# ESP-PCM1822Q1-breakout.net
KiCad netlist of a schematic drawn in Altium Designer
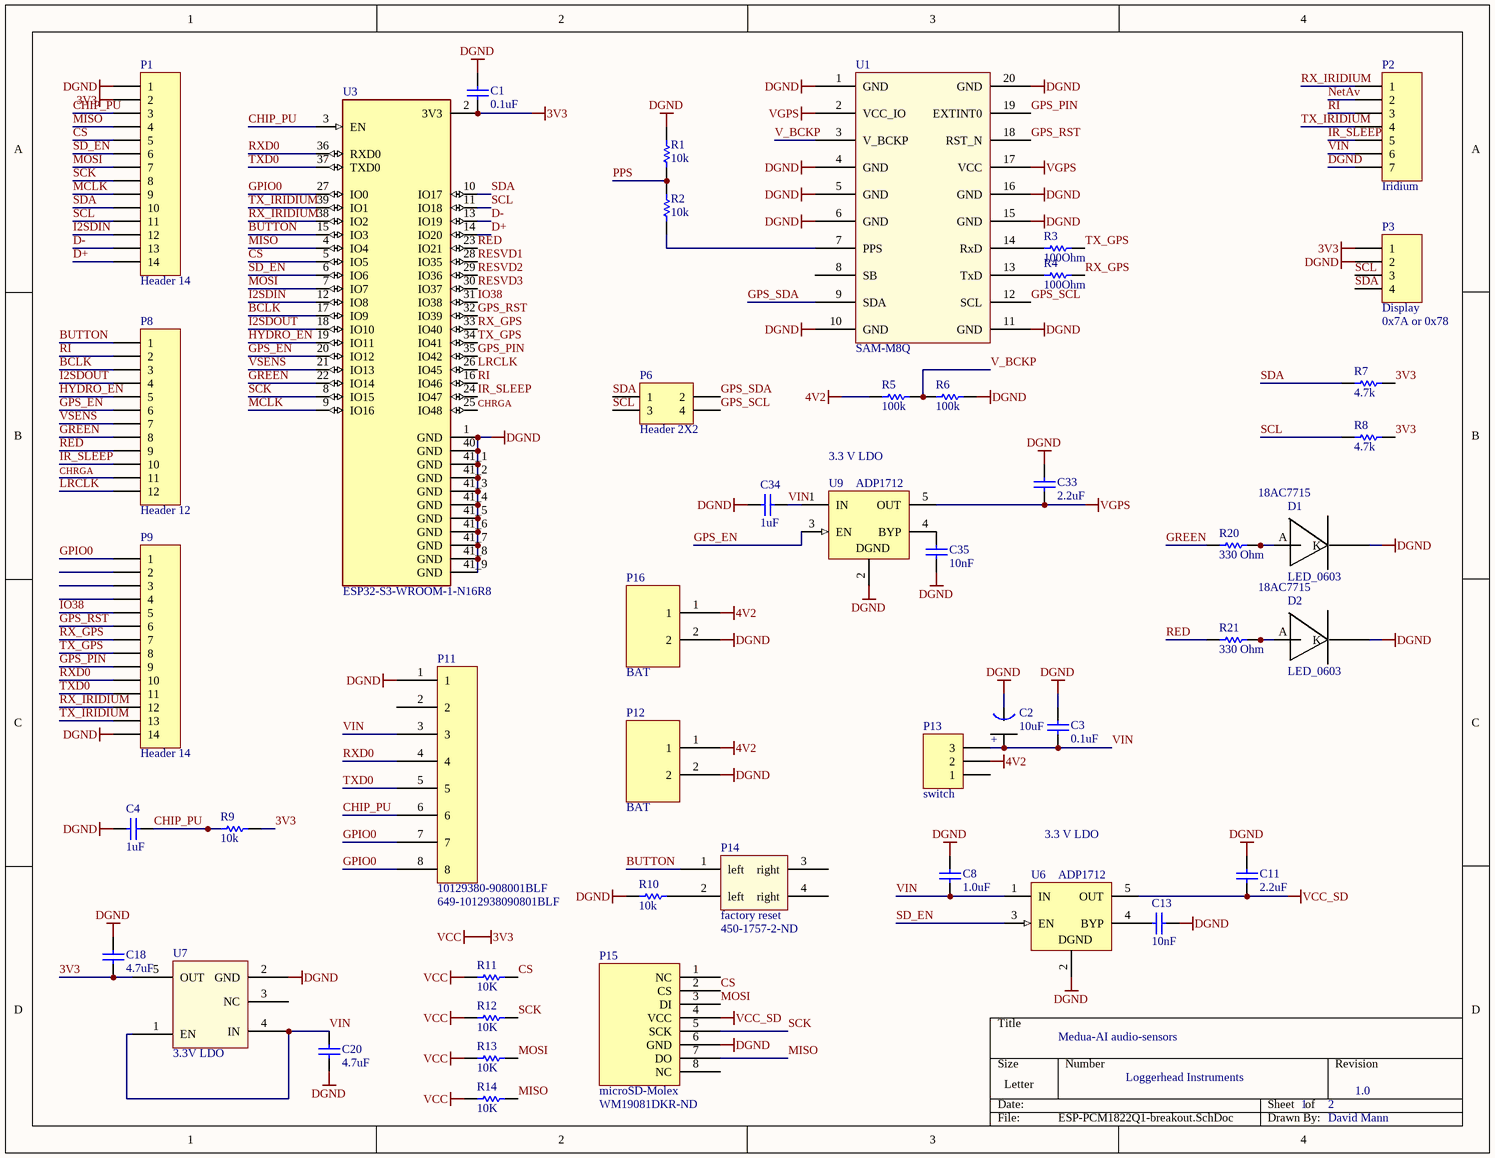
[diagram p0: ESP-PCM1822Q1-breakout.SchDoc]

(export (version "E")
  (design (tool "Eeschema 10.0.6"))
  (components
    (comp (ref "C1")
      (value "0.1uF")
      (footprint "0402")
      (description "Ceramic Chip Capacitor - Standard")
      (fields (field (name "PUBLISHER") "Altium Limited"))
      (libsource (lib "KEMET Chip Capacitor") (part "C0402"))
    )
    (comp (ref "C2") (value "10uF") (footprint "Tant0805") (libsource (lib "Loggerhead") (part "Tant0805")))
    (comp (ref "C3")
      (value "0.1uF")
      (footprint "0402")
      (description "Ceramic Chip Capacitor - Standard")
      (fields (field (name "PUBLISHER") "Altium Limited"))
      (libsource (lib "KEMET Chip Capacitor") (part "C0402"))
    )
    (comp (ref "C4")
      (value "1uF")
      (footprint "0402")
      (description "Ceramic Chip Capacitor - Standard")
      (fields (field (name "PUBLISHER") "Altium Limited"))
      (libsource (lib "KEMET Chip Capacitor") (part "C0402"))
    )
    (comp (ref "C8")
      (value "1.0uF")
      (footprint "0402")
      (description "Ceramic Chip Capacitor - Standard")
      (fields (field (name "PUBLISHER") "Altium Limited"))
      (libsource (lib "KEMET Chip Capacitor") (part "C0402"))
    )
    (comp (ref "C11")
      (value "2.2uF")
      (footprint "0402")
      (description "Ceramic Chip Capacitor - Standard")
      (fields (field (name "PUBLISHER") "Altium Limited"))
      (libsource (lib "KEMET Chip Capacitor") (part "C0402"))
    )
    (comp (ref "C13")
      (value "10nF")
      (footprint "0402")
      (description "Ceramic Chip Capacitor - Standard")
      (fields (field (name "PUBLISHER") "Altium Limited"))
      (libsource (lib "KEMET Chip Capacitor") (part "C0402"))
    )
    (comp (ref "C18")
      (value "4.7uF")
      (footprint "0402")
      (description "Ceramic Chip Capacitor - Standard")
      (fields (field (name "PUBLISHER") "Altium Limited"))
      (libsource (lib "KEMET Chip Capacitor") (part "C0402"))
    )
    (comp (ref "C20")
      (value "4.7uF")
      (footprint "0402")
      (description "Ceramic Chip Capacitor - Standard")
      (fields (field (name "PUBLISHER") "Altium Limited"))
      (libsource (lib "KEMET Chip Capacitor") (part "C0402"))
    )
    (comp (ref "C33")
      (value "2.2uF")
      (footprint "0402")
      (description "Ceramic Chip Capacitor - Standard")
      (fields (field (name "PUBLISHER") "Altium Limited"))
      (libsource (lib "KEMET Chip Capacitor") (part "C0402"))
    )
    (comp (ref "C34")
      (value "1uF")
      (footprint "0402")
      (description "Ceramic Chip Capacitor - Standard")
      (fields (field (name "PUBLISHER") "Altium Limited"))
      (libsource (lib "KEMET Chip Capacitor") (part "C0402"))
    )
    (comp (ref "C35")
      (value "10nF")
      (footprint "0402")
      (description "Ceramic Chip Capacitor - Standard")
      (fields (field (name "PUBLISHER") "Altium Limited"))
      (libsource (lib "KEMET Chip Capacitor") (part "C0402"))
    )
    (comp (ref "D1")
      (value "LED_0603")
      (footprint "Diode0603")
      (fields (field (name "SUPPLIER PART NUMBER 1") "18AC7715"))
      (libsource (lib "Loggerhead") (part "LED_0603"))
    )
    (comp (ref "D2")
      (value "LED_0603")
      (footprint "Diode0603")
      (fields (field (name "SUPPLIER PART NUMBER 1") "18AC7715"))
      (libsource (lib "Loggerhead") (part "LED_0603"))
    )
    (comp (ref "P1")
      (value "Header 14")
      (footprint "HDR1X14")
      (description "Header, 14-Pin")
      (fields (field (name "PUBLISHER") "Altium Limited"))
      (libsource (lib "Miscellaneous Connectors") (part "Header 14"))
    )
    (comp (ref "P2")
      (value "Iridium")
      (footprint "HDR1X7")
      (description "Header, 7-Pin")
      (fields (field (name "PUBLISHER") "Altium Limited"))
      (libsource (lib "Miscellaneous Connectors") (part "Header 7"))
    )
    (comp (ref "P3")
      (value "Display")
      (footprint "HDR1X4")
      (description "Header, 4-Pin")
      (fields (field (name "PUBLISHER") "Altium Limited"))
      (libsource (lib "Miscellaneous Connectors") (part "Header 4"))
    )
    (comp (ref "P6")
      (value "Header 2X2")
      (footprint "HDR2X2")
      (description "Header, 2-Pin, Dual row")
      (fields (field (name "PUBLISHER") "Altium Limited"))
      (libsource (lib "Miscellaneous Connectors") (part "Header 2X2"))
    )
    (comp (ref "P8")
      (value "Header 12")
      (footprint "HDR1X12")
      (description "Header, 12-Pin")
      (fields (field (name "PUBLISHER") "Altium Limited"))
      (libsource (lib "Miscellaneous Connectors") (part "Header 12"))
    )
    (comp (ref "P9")
      (value "Header 14")
      (footprint "HDR1X14")
      (description "Header, 14-Pin")
      (fields (field (name "PUBLISHER") "Altium Limited"))
      (libsource (lib "Miscellaneous Connectors") (part "Header 14"))
    )
    (comp (ref "P11")
      (value "10129380-908001BLF")
      (footprint "Header_8_SMT")
      (description "Surface mount header")
      (fields (field (name "SUPPLIER PART NUMBER 1") "649-1012938090801BLF"))
      (libsource (lib "Loggerhead") (part "Header8_SMT"))
    )
    (comp (ref "P12")
      (value "BAT")
      (footprint "HDR_2x1_2mm")
      (libsource (lib "Loggerhead") (part "HDR_2x1_2mm"))
    )
    (comp (ref "P13")
      (value "switch")
      (footprint "HDR1X3")
      (description "Header, 3-Pin")
      (fields (field (name "PUBLISHER") "Altium Limited"))
      (libsource (lib "Miscellaneous Connectors") (part "Header 3"))
    )
    (comp (ref "P14")
      (value "factory reset")
      (footprint "SOP4")
      (fields (field (name "SUPPLIER PART NUMBER 1") "450-1757-2-ND"))
      (libsource (lib "Loggerhead") (part "pushbutton"))
    )
    (comp (ref "P15")
      (value "microSD-Molex")
      (footprint "microSD_Molex_hinged")
      (fields (field (name "SUPPLIER PART NUMBER 1") "WM19081DKR-ND"))
      (libsource (lib "Loggerhead") (part "microSD_Molex_hinged"))
    )
    (comp (ref "P16")
      (value "BAT")
      (footprint "HDR_2x1_2mm")
      (libsource (lib "Loggerhead") (part "HDR_2x1_2mm"))
    )
    (comp (ref "R1")
      (value "10k")
      (footprint "3-0603")
      (fields (field (name "PUBLISHER") "Altium Limited"))
      (libsource (lib "Panasonic Resistor") (part "ERJ3RK"))
    )
    (comp (ref "R2")
      (value "10k")
      (footprint "3-0603")
      (fields (field (name "PUBLISHER") "Altium Limited"))
      (libsource (lib "Panasonic Resistor") (part "ERJ3RK"))
    )
    (comp (ref "R3")
      (value "100Ohm")
      (footprint "2-0402")
      (fields (field (name "PUBLISHER") "Altium Limited"))
      (libsource (lib "Panasonic Resistor") (part "ERJ2RB"))
    )
    (comp (ref "R4")
      (value "100Ohm")
      (footprint "2-0402")
      (fields (field (name "PUBLISHER") "Altium Limited"))
      (libsource (lib "Panasonic Resistor") (part "ERJ2RB"))
    )
    (comp (ref "R5")
      (value "100k")
      (footprint "3-0603")
      (fields (field (name "PUBLISHER") "Altium Limited"))
      (libsource (lib "Panasonic Resistor") (part "ERJ3RK"))
    )
    (comp (ref "R6")
      (value "100k")
      (footprint "3-0603")
      (fields (field (name "PUBLISHER") "Altium Limited"))
      (libsource (lib "Panasonic Resistor") (part "ERJ3RK"))
    )
    (comp (ref "R7")
      (value "4.7k")
      (footprint "3-0603")
      (fields (field (name "PUBLISHER") "Altium Limited"))
      (libsource (lib "Panasonic Resistor") (part "ERJ3RK"))
    )
    (comp (ref "R8")
      (value "4.7k")
      (footprint "3-0603")
      (fields (field (name "PUBLISHER") "Altium Limited"))
      (libsource (lib "Panasonic Resistor") (part "ERJ3RK"))
    )
    (comp (ref "R9")
      (value "10k")
      (footprint "2-0402")
      (fields (field (name "PUBLISHER") "Altium Limited"))
      (libsource (lib "Panasonic Resistor") (part "ERJ2RB"))
    )
    (comp (ref "R10")
      (value "10k")
      (footprint "2-0402")
      (fields (field (name "PUBLISHER") "Altium Limited"))
      (libsource (lib "Panasonic Resistor") (part "ERJ2RB"))
    )
    (comp (ref "R11")
      (value "10K")
      (footprint "3-0603")
      (fields (field (name "PUBLISHER") "Altium Limited"))
      (libsource (lib "Panasonic Resistor") (part "ERJ3EK"))
    )
    (comp (ref "R12")
      (value "10K")
      (footprint "3-0603")
      (fields (field (name "PUBLISHER") "Altium Limited"))
      (libsource (lib "Panasonic Resistor") (part "ERJ3EK"))
    )
    (comp (ref "R13")
      (value "10K")
      (footprint "3-0603")
      (fields (field (name "PUBLISHER") "Altium Limited"))
      (libsource (lib "Panasonic Resistor") (part "ERJ3EK"))
    )
    (comp (ref "R14")
      (value "10K")
      (footprint "3-0603")
      (fields (field (name "PUBLISHER") "Altium Limited"))
      (libsource (lib "Panasonic Resistor") (part "ERJ3EK"))
    )
    (comp (ref "R20")
      (value "330 Ohm")
      (footprint "2-0402")
      (fields (field (name "PUBLISHER") "Altium Limited"))
      (libsource (lib "Panasonic Resistor") (part "ERJ2RB"))
    )
    (comp (ref "R21")
      (value "330 Ohm")
      (footprint "2-0402")
      (fields (field (name "PUBLISHER") "Altium Limited"))
      (libsource (lib "Panasonic Resistor") (part "ERJ2RB"))
    )
    (comp (ref "U1")
      (value "SAM-M8Q")
      (footprint "GPS SAM-MQ8")
      (libsource (lib "Loggerhead") (part "GPS SAM-M8Q"))
    )
    (comp (ref "U3")
      (value "ESP32-S3-WROOM-1-N16R8")
      (footprint "XCVR_ESP32-S3-WROOM-1-N16R2")
      (description "Bluetooth, WiFi 802.11b/g/n, Bluetooth v5.0 Transceiver Module 2.4GHz PCB Trace Surface Mount")
      (fields (field (name "MP") "ESP32-S3-WROOM-1-N16R2") (field (name "MF") "Espressif Systems"))
      (libsource (lib "ESP32-S3-WROOM-1-N16R2") (part "ESP32-S3-WROOM-1-N16R2"))
    )
    (comp (ref "U6")
      (value "ADP1712")
      (footprint "MF05A_N")
      (description "Micropower, 150mA Low-Noise Ultra Low-Dropout CMOS Voltage Regulator")
      (fields
        (field (name "PARTNUMBER") "LP3985IM5-3.3")
        (field (name "MANUFACTURER") "National Semiconductor")
        (field (name "PUBLISHER") "Altium Limited")
      )
      (libsource (lib "NSC LDO") (part "LP3985IM5-3.3"))
    )
    (comp (ref "U7")
      (value "3.3V LDO")
      (footprint "AP7361C-33Y5-13")
      (libsource (lib "Loggerhead") (part "AP7361C-33Y5-13"))
    )
    (comp (ref "U9")
      (value "ADP1712")
      (footprint "MF05A_N")
      (description "Micropower, 150mA Low-Noise Ultra Low-Dropout CMOS Voltage Regulator")
      (fields
        (field (name "PARTNUMBER") "LP3985IM5-3.3")
        (field (name "MANUFACTURER") "National Semiconductor")
        (field (name "PUBLISHER") "Altium Limited")
      )
      (libsource (lib "NSC LDO") (part "LP3985IM5-3.3"))
    )
  )
  (nets
    (net (code "1") (name "/BCLK") (class "Default")
      (node (ref "P8") (pin "3") (pinfunction "3_3") (pintype "passive"))
      (node (ref "U3") (pin "17") (pinfunction "IO9_17") (pintype "bidirectional"))
    )
    (net (code "2") (name "/BUTTON") (class "Default")
      (node (ref "P14") (pin "1") (pinfunction "left_1") (pintype "passive"))
      (node (ref "P8") (pin "1") (pinfunction "1_1") (pintype "passive"))
      (node (ref "U3") (pin "15") (pinfunction "IO3_15") (pintype "bidirectional"))
    )
    (net (code "3") (name "/CHIP_PU") (class "Default")
      (node (ref "C4") (pin "1") (pinfunction "1_1") (pintype "passive"))
      (node (ref "P1") (pin "3") (pinfunction "3_3") (pintype "passive"))
      (node (ref "P11") (pin "6") (pinfunction "6_6") (pintype "passive"))
      (node (ref "R9") (pin "2") (pinfunction "2_2") (pintype "passive"))
      (node (ref "U3") (pin "3") (pinfunction "EN_3") (pintype "input"))
    )
    (net (code "4") (name "/CHRGA") (class "Default")
      (node (ref "P8") (pin "11") (pinfunction "11_11") (pintype "passive"))
      (node (ref "U3") (pin "25") (pinfunction "IO48_25") (pintype "bidirectional"))
    )
    (net (code "5") (name "/CS") (class "Default")
      (node (ref "P1") (pin "5") (pinfunction "5_5") (pintype "passive"))
      (node (ref "P15") (pin "2") (pinfunction "CS_2") (pintype "passive"))
      (node (ref "R11") (pin "2") (pinfunction "2_2") (pintype "passive"))
      (node (ref "U3") (pin "5") (pinfunction "IO5_5") (pintype "bidirectional"))
    )
    (net (code "6") (name "/D+") (class "Default")
      (node (ref "P1") (pin "14") (pinfunction "14_14") (pintype "passive"))
      (node (ref "U3") (pin "14") (pinfunction "IO20_14") (pintype "bidirectional"))
    )
    (net (code "7") (name "/D-") (class "Default")
      (node (ref "P1") (pin "13") (pinfunction "13_13") (pintype "passive"))
      (node (ref "U3") (pin "13") (pinfunction "IO19_13") (pintype "bidirectional"))
    )
    (net (code "8") (name "/GPIO0") (class "Default")
      (node (ref "P11") (pin "7") (pinfunction "7_7") (pintype "passive"))
      (node (ref "P11") (pin "8") (pinfunction "8_8") (pintype "passive"))
      (node (ref "P9") (pin "1") (pinfunction "1_1") (pintype "passive"))
      (node (ref "U3") (pin "27") (pinfunction "IO0_27") (pintype "bidirectional"))
    )
    (net (code "9") (name "/GPS_EN") (class "Default")
      (node (ref "P8") (pin "6") (pinfunction "6_6") (pintype "passive"))
      (node (ref "U3") (pin "20") (pinfunction "IO12_20") (pintype "bidirectional"))
      (node (ref "U9") (pin "3") (pinfunction "EN_3") (pintype "input"))
    )
    (net (code "10") (name "/GPS_PIN") (class "Default")
      (node (ref "P9") (pin "9") (pinfunction "9_9") (pintype "passive"))
      (node (ref "U1") (pin "19") (pinfunction "EXTINT0_19") (pintype "passive"))
      (node (ref "U3") (pin "35") (pinfunction "IO42_35") (pintype "bidirectional"))
    )
    (net (code "11") (name "/GPS_RST") (class "Default")
      (node (ref "P9") (pin "6") (pinfunction "6_6") (pintype "passive"))
      (node (ref "U1") (pin "18") (pinfunction "RST_N_18") (pintype "passive"))
      (node (ref "U3") (pin "32") (pinfunction "IO39_32") (pintype "bidirectional"))
    )
    (net (code "12") (name "/GPS_SCL") (class "Default")
      (node (ref "P6") (pin "4") (pinfunction "4_4") (pintype "passive"))
      (node (ref "U1") (pin "12") (pinfunction "SCL_12") (pintype "passive"))
    )
    (net (code "13") (name "/GPS_SDA") (class "Default")
      (node (ref "P6") (pin "2") (pinfunction "2_2") (pintype "passive"))
      (node (ref "U1") (pin "9") (pinfunction "SDA_9") (pintype "passive"))
    )
    (net (code "14") (name "/GREEN") (class "Default")
      (node (ref "P8") (pin "8") (pinfunction "8_8") (pintype "passive"))
      (node (ref "R20") (pin "2") (pinfunction "2_2") (pintype "passive"))
      (node (ref "U3") (pin "22") (pinfunction "IO14_22") (pintype "bidirectional"))
    )
    (net (code "15") (name "/HYDRO_EN") (class "Default")
      (node (ref "P8") (pin "5") (pinfunction "5_5") (pintype "passive"))
      (node (ref "U3") (pin "19") (pinfunction "IO11_19") (pintype "bidirectional"))
    )
    (net (code "16") (name "/I2SDIN") (class "Default")
      (node (ref "P1") (pin "12") (pinfunction "12_12") (pintype "passive"))
      (node (ref "U3") (pin "12") (pinfunction "IO8_12") (pintype "bidirectional"))
    )
    (net (code "17") (name "/I2SDOUT") (class "Default")
      (node (ref "P8") (pin "4") (pinfunction "4_4") (pintype "passive"))
      (node (ref "U3") (pin "18") (pinfunction "IO10_18") (pintype "bidirectional"))
    )
    (net (code "18") (name "/IO38") (class "Default")
      (node (ref "P9") (pin "5") (pinfunction "5_5") (pintype "passive"))
      (node (ref "U3") (pin "31") (pinfunction "IO38_31") (pintype "bidirectional"))
    )
    (net (code "19") (name "/IR_SLEEP") (class "Default")
      (node (ref "P2") (pin "5") (pinfunction "5_5") (pintype "passive"))
      (node (ref "P8") (pin "10") (pinfunction "10_10") (pintype "passive"))
      (node (ref "U3") (pin "24") (pinfunction "IO47_24") (pintype "bidirectional"))
    )
    (net (code "20") (name "/LRCLK") (class "Default")
      (node (ref "P8") (pin "12") (pinfunction "12_12") (pintype "passive"))
      (node (ref "U3") (pin "26") (pinfunction "IO45_26") (pintype "bidirectional"))
    )
    (net (code "21") (name "/MCLK") (class "Default")
      (node (ref "P1") (pin "9") (pinfunction "9_9") (pintype "passive"))
      (node (ref "U3") (pin "9") (pinfunction "IO16_9") (pintype "bidirectional"))
    )
    (net (code "22") (name "/MISO") (class "Default")
      (node (ref "P1") (pin "4") (pinfunction "4_4") (pintype "passive"))
      (node (ref "P15") (pin "7") (pinfunction "DO_7") (pintype "passive"))
      (node (ref "R14") (pin "2") (pinfunction "2_2") (pintype "passive"))
      (node (ref "U3") (pin "4") (pinfunction "IO4_4") (pintype "bidirectional"))
    )
    (net (code "23") (name "/MOSI") (class "Default")
      (node (ref "P1") (pin "7") (pinfunction "7_7") (pintype "passive"))
      (node (ref "P15") (pin "3") (pinfunction "DI_3") (pintype "passive"))
      (node (ref "R13") (pin "2") (pinfunction "2_2") (pintype "passive"))
      (node (ref "U3") (pin "7") (pinfunction "IO7_7") (pintype "bidirectional"))
    )
    (net (code "24") (name "/NetAv") (class "Default")
      (node (ref "P2") (pin "2") (pinfunction "2_2") (pintype "passive"))
    )
    (net (code "25") (name "/PPS") (class "Default")
      (node (ref "R1") (pin "2") (pinfunction "2_2") (pintype "passive"))
      (node (ref "R2") (pin "1") (pinfunction "1_1") (pintype "passive"))
    )
    (net (code "26") (name "/RED") (class "Default")
      (node (ref "P8") (pin "9") (pinfunction "9_9") (pintype "passive"))
      (node (ref "R21") (pin "2") (pinfunction "2_2") (pintype "passive"))
      (node (ref "U3") (pin "23") (pinfunction "IO21_23") (pintype "bidirectional"))
    )
    (net (code "27") (name "/RESVD1") (class "Default")
      (node (ref "U3") (pin "28") (pinfunction "IO35_28") (pintype "bidirectional"))
    )
    (net (code "28") (name "/RESVD2") (class "Default")
      (node (ref "U3") (pin "29") (pinfunction "IO36_29") (pintype "bidirectional"))
    )
    (net (code "29") (name "/RESVD3") (class "Default")
      (node (ref "U3") (pin "30") (pinfunction "IO37_30") (pintype "bidirectional"))
    )
    (net (code "30") (name "/RI") (class "Default")
      (node (ref "P2") (pin "3") (pinfunction "3_3") (pintype "passive"))
      (node (ref "P8") (pin "2") (pinfunction "2_2") (pintype "passive"))
      (node (ref "U3") (pin "16") (pinfunction "IO46_16") (pintype "bidirectional"))
    )
    (net (code "31") (name "/RXD0") (class "Default")
      (node (ref "P11") (pin "4") (pinfunction "4_4") (pintype "passive"))
      (node (ref "P9") (pin "10") (pinfunction "10_10") (pintype "passive"))
      (node (ref "U3") (pin "36") (pinfunction "RXD0_36") (pintype "bidirectional"))
    )
    (net (code "32") (name "/RX_GPS") (class "Default")
      (node (ref "P9") (pin "7") (pinfunction "7_7") (pintype "passive"))
      (node (ref "R4") (pin "1") (pinfunction "1_1") (pintype "passive"))
      (node (ref "U3") (pin "33") (pinfunction "IO40_33") (pintype "bidirectional"))
    )
    (net (code "33") (name "/RX_IRIDIUM") (class "Default")
      (node (ref "P2") (pin "1") (pinfunction "1_1") (pintype "passive"))
      (node (ref "P9") (pin "12") (pinfunction "12_12") (pintype "passive"))
      (node (ref "U3") (pin "38") (pinfunction "IO2_38") (pintype "bidirectional"))
    )
    (net (code "34") (name "/SCK") (class "Default")
      (node (ref "P1") (pin "8") (pinfunction "8_8") (pintype "passive"))
      (node (ref "P15") (pin "5") (pinfunction "SCK_5") (pintype "passive"))
      (node (ref "R12") (pin "2") (pinfunction "2_2") (pintype "passive"))
      (node (ref "U3") (pin "8") (pinfunction "IO15_8") (pintype "bidirectional"))
    )
    (net (code "35") (name "/SCL") (class "Default")
      (node (ref "P1") (pin "11") (pinfunction "11_11") (pintype "passive"))
      (node (ref "P3") (pin "3") (pinfunction "3_3") (pintype "passive"))
      (node (ref "P6") (pin "3") (pinfunction "3_3") (pintype "passive"))
      (node (ref "R8") (pin "1") (pinfunction "1_1") (pintype "passive"))
      (node (ref "U3") (pin "11") (pinfunction "IO18_11") (pintype "bidirectional"))
    )
    (net (code "36") (name "/SDA") (class "Default")
      (node (ref "P1") (pin "10") (pinfunction "10_10") (pintype "passive"))
      (node (ref "P3") (pin "4") (pinfunction "4_4") (pintype "passive"))
      (node (ref "P6") (pin "1") (pinfunction "1_1") (pintype "passive"))
      (node (ref "R7") (pin "1") (pinfunction "1_1") (pintype "passive"))
      (node (ref "U3") (pin "10") (pinfunction "IO17_10") (pintype "bidirectional"))
    )
    (net (code "37") (name "/SD_EN") (class "Default")
      (node (ref "P1") (pin "6") (pinfunction "6_6") (pintype "passive"))
      (node (ref "U3") (pin "6") (pinfunction "IO6_6") (pintype "bidirectional"))
      (node (ref "U6") (pin "3") (pinfunction "EN_3") (pintype "input"))
    )
    (net (code "38") (name "/TXD0") (class "Default")
      (node (ref "P11") (pin "5") (pinfunction "5_5") (pintype "passive"))
      (node (ref "P9") (pin "11") (pinfunction "11_11") (pintype "passive"))
      (node (ref "U3") (pin "37") (pinfunction "TXD0_37") (pintype "bidirectional"))
    )
    (net (code "39") (name "/TX_GPS") (class "Default")
      (node (ref "P9") (pin "8") (pinfunction "8_8") (pintype "passive"))
      (node (ref "R3") (pin "1") (pinfunction "1_1") (pintype "passive"))
      (node (ref "U3") (pin "34") (pinfunction "IO41_34") (pintype "bidirectional"))
    )
    (net (code "40") (name "/TX_IRIDIUM") (class "Default")
      (node (ref "P2") (pin "4") (pinfunction "4_4") (pintype "passive"))
      (node (ref "P9") (pin "13") (pinfunction "13_13") (pintype "passive"))
      (node (ref "U3") (pin "39") (pinfunction "IO1_39") (pintype "bidirectional"))
    )
    (net (code "41") (name "/VIN") (class "Default")
      (node (ref "C2") (pin "2") (pinfunction "+_2") (pintype "passive"))
      (node (ref "C20") (pin "1") (pinfunction "1_1") (pintype "passive"))
      (node (ref "C3") (pin "1") (pinfunction "1_1") (pintype "passive"))
      (node (ref "C34") (pin "1") (pinfunction "1_1") (pintype "passive"))
      (node (ref "C8") (pin "1") (pinfunction "1_1") (pintype "passive"))
      (node (ref "P11") (pin "3") (pinfunction "3_3") (pintype "passive"))
      (node (ref "P13") (pin "3") (pinfunction "3_3") (pintype "passive"))
      (node (ref "P2") (pin "6") (pinfunction "6_6") (pintype "passive"))
      (node (ref "U6") (pin "1") (pinfunction "IN_1") (pintype "power_in"))
      (node (ref "U7") (pin "1") (pinfunction "EN_1") (pintype "passive"))
      (node (ref "U7") (pin "4") (pinfunction "IN_4") (pintype "passive"))
      (node (ref "U9") (pin "1") (pinfunction "IN_1") (pintype "power_in"))
    )
    (net (code "42") (name "/VSENS") (class "Default")
      (node (ref "P8") (pin "7") (pinfunction "7_7") (pintype "passive"))
      (node (ref "U3") (pin "21") (pinfunction "IO13_21") (pintype "bidirectional"))
    )
    (net (code "43") (name "/V_BCKP") (class "Default")
      (node (ref "R5") (pin "1") (pinfunction "1_1") (pintype "passive"))
      (node (ref "R6") (pin "2") (pinfunction "2_2") (pintype "passive"))
      (node (ref "U1") (pin "3") (pinfunction "V_BCKP_3") (pintype "passive"))
    )
    (net (code "44") (name "3V3") (class "Default")
      (node (ref "C1") (pin "1") (pinfunction "1_1") (pintype "passive"))
      (node (ref "C18") (pin "2") (pinfunction "2_2") (pintype "passive"))
      (node (ref "P1") (pin "2") (pinfunction "2_2") (pintype "passive"))
      (node (ref "P3") (pin "1") (pinfunction "1_1") (pintype "passive"))
      (node (ref "R11") (pin "1") (pinfunction "1_1") (pintype "passive"))
      (node (ref "R12") (pin "1") (pinfunction "1_1") (pintype "passive"))
      (node (ref "R13") (pin "1") (pinfunction "1_1") (pintype "passive"))
      (node (ref "R14") (pin "1") (pinfunction "1_1") (pintype "passive"))
      (node (ref "R7") (pin "2") (pinfunction "2_2") (pintype "passive"))
      (node (ref "R8") (pin "2") (pinfunction "2_2") (pintype "passive"))
      (node (ref "R9") (pin "1") (pinfunction "1_1") (pintype "passive"))
      (node (ref "U3") (pin "2") (pinfunction "3V3_2") (pintype "power_in"))
      (node (ref "U7") (pin "5") (pinfunction "OUT_5") (pintype "passive"))
    )
    (net (code "45") (name "4V2") (class "Default")
      (node (ref "P12") (pin "1") (pinfunction "1_1") (pintype "passive"))
      (node (ref "P13") (pin "2") (pinfunction "2_2") (pintype "passive"))
      (node (ref "P16") (pin "1") (pinfunction "1_1") (pintype "passive"))
      (node (ref "R5") (pin "2") (pinfunction "2_2") (pintype "passive"))
    )
    (net (code "46") (name "DGND") (class "Default")
      (node (ref "C1") (pin "2") (pinfunction "2_2") (pintype "passive"))
      (node (ref "C11") (pin "2") (pinfunction "2_2") (pintype "passive"))
      (node (ref "C13") (pin "1") (pinfunction "1_1") (pintype "passive"))
      (node (ref "C18") (pin "1") (pinfunction "1_1") (pintype "passive"))
      (node (ref "C2") (pin "1") (pinfunction "GND_1") (pintype "passive"))
      (node (ref "C20") (pin "2") (pinfunction "2_2") (pintype "passive"))
      (node (ref "C3") (pin "2") (pinfunction "2_2") (pintype "passive"))
      (node (ref "C33") (pin "2") (pinfunction "2_2") (pintype "passive"))
      (node (ref "C34") (pin "2") (pinfunction "2_2") (pintype "passive"))
      (node (ref "C35") (pin "2") (pinfunction "2_2") (pintype "passive"))
      (node (ref "C4") (pin "2") (pinfunction "2_2") (pintype "passive"))
      (node (ref "C8") (pin "2") (pinfunction "2_2") (pintype "passive"))
      (node (ref "D1") (pin "K") (pinfunction "K_K") (pintype "passive"))
      (node (ref "D2") (pin "K") (pinfunction "K_K") (pintype "passive"))
      (node (ref "P1") (pin "1") (pinfunction "1_1") (pintype "passive"))
      (node (ref "P11") (pin "1") (pinfunction "1_1") (pintype "passive"))
      (node (ref "P12") (pin "2") (pinfunction "2_2") (pintype "passive"))
      (node (ref "P15") (pin "6") (pinfunction "GND_6") (pintype "passive"))
      (node (ref "P16") (pin "2") (pinfunction "2_2") (pintype "passive"))
      (node (ref "P2") (pin "7") (pinfunction "7_7") (pintype "passive"))
      (node (ref "P3") (pin "2") (pinfunction "2_2") (pintype "passive"))
      (node (ref "P9") (pin "14") (pinfunction "14_14") (pintype "passive"))
      (node (ref "R1") (pin "1") (pinfunction "1_1") (pintype "passive"))
      (node (ref "R10") (pin "2") (pinfunction "2_2") (pintype "passive"))
      (node (ref "R6") (pin "1") (pinfunction "1_1") (pintype "passive"))
      (node (ref "U1") (pin "1") (pinfunction "GND_1") (pintype "passive"))
      (node (ref "U1") (pin "10") (pinfunction "GND_10") (pintype "passive"))
      (node (ref "U1") (pin "11") (pinfunction "GND_11") (pintype "passive"))
      (node (ref "U1") (pin "15") (pinfunction "GND_15") (pintype "passive"))
      (node (ref "U1") (pin "16") (pinfunction "GND_16") (pintype "passive"))
      (node (ref "U1") (pin "20") (pinfunction "GND_20") (pintype "passive"))
      (node (ref "U1") (pin "4") (pinfunction "GND_4") (pintype "passive"))
      (node (ref "U1") (pin "5") (pinfunction "GND_5") (pintype "passive"))
      (node (ref "U1") (pin "6") (pinfunction "GND_6") (pintype "passive"))
      (node (ref "U3") (pin "1") (pinfunction "GND_1") (pintype "power_in"))
      (node (ref "U3") (pin "40") (pinfunction "GND_40") (pintype "power_in"))
      (node (ref "U3") (pin "41_1") (pinfunction "GND_41_1") (pintype "power_in"))
      (node (ref "U3") (pin "41_2") (pinfunction "GND_41_2") (pintype "power_in"))
      (node (ref "U3") (pin "41_3") (pinfunction "GND_41_3") (pintype "power_in"))
      (node (ref "U3") (pin "41_4") (pinfunction "GND_41_4") (pintype "power_in"))
      (node (ref "U3") (pin "41_5") (pinfunction "GND_41_5") (pintype "power_in"))
      (node (ref "U3") (pin "41_6") (pinfunction "GND_41_6") (pintype "power_in"))
      (node (ref "U3") (pin "41_7") (pinfunction "GND_41_7") (pintype "power_in"))
      (node (ref "U3") (pin "41_8") (pinfunction "GND_41_8") (pintype "power_in"))
      (node (ref "U3") (pin "41_9") (pinfunction "GND_41_9") (pintype "power_in"))
      (node (ref "U6") (pin "2") (pinfunction "GND_2") (pintype "power_in"))
      (node (ref "U7") (pin "2") (pinfunction "GND_2") (pintype "passive"))
      (node (ref "U9") (pin "2") (pinfunction "GND_2") (pintype "power_in"))
    )
    (net (code "47") (name "Net-(D1-PadA)") (class "Default")
      (node (ref "D1") (pin "A") (pinfunction "A_A") (pintype "passive"))
      (node (ref "R20") (pin "1") (pinfunction "1_1") (pintype "passive"))
    )
    (net (code "48") (name "Net-(D2-PadA)") (class "Default")
      (node (ref "D2") (pin "A") (pinfunction "A_A") (pintype "passive"))
      (node (ref "R21") (pin "1") (pinfunction "1_1") (pintype "passive"))
    )
    (net (code "49") (name "Net-(P14-left-Pad2)") (class "Default")
      (node (ref "P14") (pin "2") (pinfunction "left_2") (pintype "passive"))
      (node (ref "R10") (pin "1") (pinfunction "1_1") (pintype "passive"))
    )
    (net (code "50") (name "Net-(U1-PPS)") (class "Default")
      (node (ref "R2") (pin "2") (pinfunction "2_2") (pintype "passive"))
      (node (ref "U1") (pin "7") (pinfunction "PPS_7") (pintype "passive"))
    )
    (net (code "51") (name "Net-(U1-RxD)") (class "Default")
      (node (ref "R3") (pin "2") (pinfunction "2_2") (pintype "passive"))
      (node (ref "U1") (pin "14") (pinfunction "RxD_14") (pintype "passive"))
    )
    (net (code "52") (name "Net-(U1-TxD)") (class "Default")
      (node (ref "R4") (pin "2") (pinfunction "2_2") (pintype "passive"))
      (node (ref "U1") (pin "13") (pinfunction "TxD_13") (pintype "passive"))
    )
    (net (code "53") (name "Net-(U6-BYP)") (class "Default")
      (node (ref "C13") (pin "2") (pinfunction "2_2") (pintype "passive"))
      (node (ref "U6") (pin "4") (pinfunction "BYP_4") (pintype "passive"))
    )
    (net (code "54") (name "Net-(U9-BYP)") (class "Default")
      (node (ref "C35") (pin "1") (pinfunction "1_1") (pintype "passive"))
      (node (ref "U9") (pin "4") (pinfunction "BYP_4") (pintype "passive"))
    )
    (net (code "55") (name "VCC_SD") (class "Default")
      (node (ref "C11") (pin "1") (pinfunction "1_1") (pintype "passive"))
      (node (ref "P15") (pin "4") (pinfunction "VCC_4") (pintype "passive"))
      (node (ref "U6") (pin "5") (pinfunction "OUT_5") (pintype "power_in"))
    )
    (net (code "56") (name "VGPS") (class "Default")
      (node (ref "C33") (pin "1") (pinfunction "1_1") (pintype "passive"))
      (node (ref "U1") (pin "17") (pinfunction "VCC_17") (pintype "passive"))
      (node (ref "U1") (pin "2") (pinfunction "VCC_IO_2") (pintype "passive"))
      (node (ref "U9") (pin "5") (pinfunction "OUT_5") (pintype "power_in"))
    )
    (net (code "57") (name "unconnected-(P9-Pad2)") (class "Default")
      (node (ref "P9") (pin "2") (pinfunction "2_2") (pintype "passive"))
    )
    (net (code "58") (name "unconnected-(P9-Pad3)") (class "Default")
      (node (ref "P9") (pin "3") (pinfunction "3_3") (pintype "passive"))
    )
    (net (code "59") (name "unconnected-(P9-Pad4)") (class "Default")
      (node (ref "P9") (pin "4") (pinfunction "4_4") (pintype "passive"))
    )
    (net (code "60") (name "unconnected-(P11-Pad2)") (class "Default")
      (node (ref "P11") (pin "2") (pinfunction "2_2") (pintype "passive"))
    )
    (net (code "61") (name "unconnected-(P13-Pad1)") (class "Default")
      (node (ref "P13") (pin "1") (pinfunction "1_1") (pintype "passive"))
    )
    (net (code "62") (name "unconnected-(P14-right-Pad3)") (class "Default")
      (node (ref "P14") (pin "3") (pinfunction "right_3") (pintype "passive"))
    )
    (net (code "63") (name "unconnected-(P14-right-Pad4)") (class "Default")
      (node (ref "P14") (pin "4") (pinfunction "right_4") (pintype "passive"))
    )
    (net (code "64") (name "unconnected-(P15-NC-Pad1)") (class "Default")
      (node (ref "P15") (pin "1") (pinfunction "NC_1") (pintype "passive"))
    )
    (net (code "65") (name "unconnected-(P15-NC-Pad8)") (class "Default")
      (node (ref "P15") (pin "8") (pinfunction "NC_8") (pintype "passive"))
    )
    (net (code "66") (name "unconnected-(U1-SB-Pad8)") (class "Default")
      (node (ref "U1") (pin "8") (pinfunction "SB_8") (pintype "passive"))
    )
    (net (code "67") (name "unconnected-(U7-NC-Pad3)") (class "Default")
      (node (ref "U7") (pin "3") (pinfunction "NC_3") (pintype "passive"))
    )
  )
)
